# AUDIO_IN_OUT.net
KiCad netlist of a schematic drawn in Altium Designer
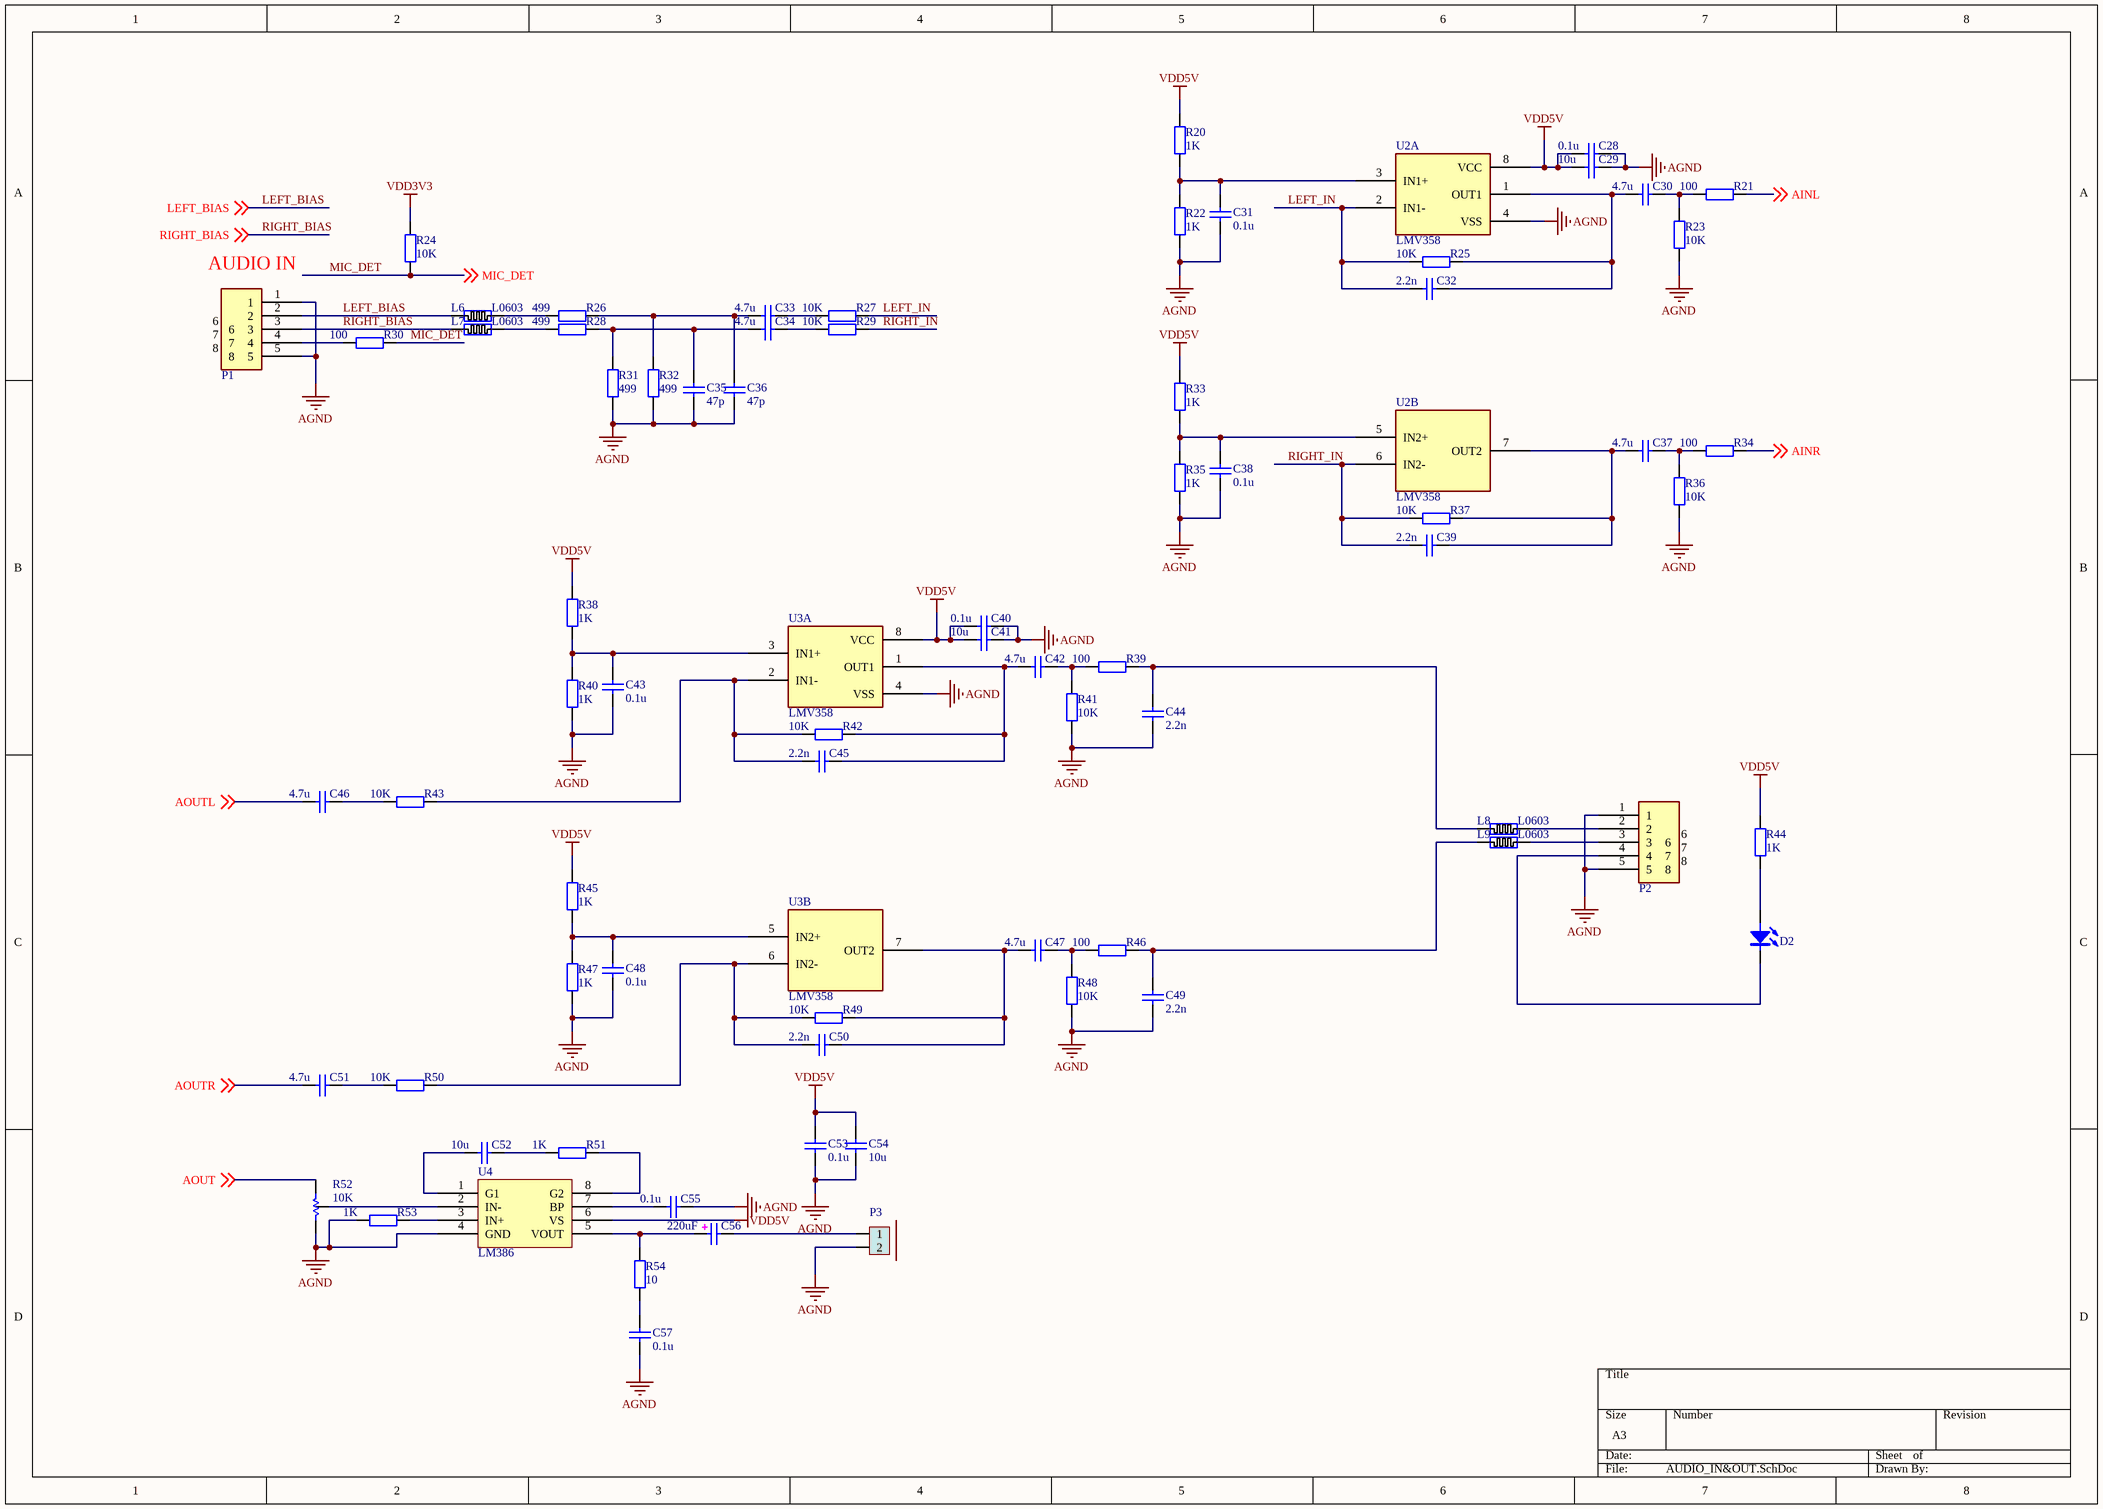
[diagram p0: AUDIO_IN&OUT.SchDoc]

(export (version "E")
  (design (tool "Eeschema 10.0.6"))
  (components
    (comp (ref "C28")
      (value "0.1u")
      (footprint "C0603")
      (description "0603 Capacitor without Polarity")
      (libsource (lib "lpc2368") (part "CAP0603"))
    )
    (comp (ref "C29")
      (value "10u")
      (footprint "C0603")
      (description "0603 Capacitor without Polarity")
      (libsource (lib "lpc2368") (part "CAP0603"))
    )
    (comp (ref "C30")
      (value "4.7u")
      (footprint "C0603")
      (description "0603 Capacitor without Polarity")
      (libsource (lib "lpc2368") (part "CAP0603"))
    )
    (comp (ref "C31")
      (value "0.1u")
      (footprint "C0603")
      (description "0603 Capacitor without Polarity")
      (libsource (lib "lpc2368") (part "CAP0603"))
    )
    (comp (ref "C32")
      (value "2.2n")
      (footprint "C0603")
      (description "0603 Capacitor without Polarity")
      (libsource (lib "lpc2368") (part "CAP0603"))
    )
    (comp (ref "C33")
      (value "4.7u")
      (footprint "C0603")
      (description "0603 Capacitor without Polarity")
      (libsource (lib "lpc2368") (part "CAP0603"))
    )
    (comp (ref "C34")
      (value "4.7u")
      (footprint "C0603")
      (description "0603 Capacitor without Polarity")
      (libsource (lib "lpc2368") (part "CAP0603"))
    )
    (comp (ref "C35")
      (value "47p")
      (footprint "C0603")
      (description "0603 Capacitor without Polarity")
      (libsource (lib "lpc2368") (part "CAP0603"))
    )
    (comp (ref "C36")
      (value "47p")
      (footprint "C0603")
      (description "0603 Capacitor without Polarity")
      (libsource (lib "lpc2368") (part "CAP0603"))
    )
    (comp (ref "C37")
      (value "4.7u")
      (footprint "C0603")
      (description "0603 Capacitor without Polarity")
      (libsource (lib "lpc2368") (part "CAP0603"))
    )
    (comp (ref "C38")
      (value "0.1u")
      (footprint "C0603")
      (description "0603 Capacitor without Polarity")
      (libsource (lib "lpc2368") (part "CAP0603"))
    )
    (comp (ref "C39")
      (value "2.2n")
      (footprint "C0603")
      (description "0603 Capacitor without Polarity")
      (libsource (lib "lpc2368") (part "CAP0603"))
    )
    (comp (ref "C40")
      (value "0.1u")
      (footprint "C0603")
      (description "0603 Capacitor without Polarity")
      (libsource (lib "lpc2368") (part "CAP0603"))
    )
    (comp (ref "C41")
      (value "10u")
      (footprint "C0603")
      (description "0603 Capacitor without Polarity")
      (libsource (lib "lpc2368") (part "CAP0603"))
    )
    (comp (ref "C42")
      (value "4.7u")
      (footprint "C0603")
      (description "0603 Capacitor without Polarity")
      (libsource (lib "lpc2368") (part "CAP0603"))
    )
    (comp (ref "C43")
      (value "0.1u")
      (footprint "C0603")
      (description "0603 Capacitor without Polarity")
      (libsource (lib "lpc2368") (part "CAP0603"))
    )
    (comp (ref "C44")
      (value "2.2n")
      (footprint "C0603")
      (description "0603 Capacitor without Polarity")
      (libsource (lib "lpc2368") (part "CAP0603"))
    )
    (comp (ref "C45")
      (value "2.2n")
      (footprint "C0603")
      (description "0603 Capacitor without Polarity")
      (libsource (lib "lpc2368") (part "CAP0603"))
    )
    (comp (ref "C46")
      (value "4.7u")
      (footprint "C0603")
      (description "0603 Capacitor without Polarity")
      (libsource (lib "lpc2368") (part "CAP0603"))
    )
    (comp (ref "C47")
      (value "4.7u")
      (footprint "C0603")
      (description "0603 Capacitor without Polarity")
      (libsource (lib "lpc2368") (part "CAP0603"))
    )
    (comp (ref "C48")
      (value "0.1u")
      (footprint "C0603")
      (description "0603 Capacitor without Polarity")
      (libsource (lib "lpc2368") (part "CAP0603"))
    )
    (comp (ref "C49")
      (value "2.2n")
      (footprint "C0603")
      (description "0603 Capacitor without Polarity")
      (libsource (lib "lpc2368") (part "CAP0603"))
    )
    (comp (ref "C50")
      (value "2.2n")
      (footprint "C0603")
      (description "0603 Capacitor without Polarity")
      (libsource (lib "lpc2368") (part "CAP0603"))
    )
    (comp (ref "C51")
      (value "4.7u")
      (footprint "C0603")
      (description "0603 Capacitor without Polarity")
      (libsource (lib "lpc2368") (part "CAP0603"))
    )
    (comp (ref "C52")
      (value "10u")
      (footprint "C0603")
      (description "0603 Capacitor without Polarity")
      (libsource (lib "lpc2368") (part "CAP0603"))
    )
    (comp (ref "C53")
      (value "0.1u")
      (footprint "C0603")
      (description "0603 Capacitor without Polarity")
      (libsource (lib "lpc2368") (part "CAP0603"))
    )
    (comp (ref "C54")
      (value "10u")
      (footprint "C0603")
      (description "0603 Capacitor without Polarity")
      (libsource (lib "lpc2368") (part "CAP0603"))
    )
    (comp (ref "C55")
      (value "0.1u")
      (footprint "C0603")
      (description "0603 Capacitor without Polarity")
      (libsource (lib "lpc2368") (part "CAP0603"))
    )
    (comp (ref "C56")
      (value "220uF")
      (footprint "tc")
      (description "钽电容1210封装")
      (libsource (lib "lpc2368") (part "DCAP"))
    )
    (comp (ref "C57")
      (value "0.1u")
      (footprint "C0603")
      (description "0603 Capacitor without Polarity")
      (libsource (lib "lpc2368") (part "CAP0603"))
    )
    (comp (ref "D2")
      (value "LED_SMT")
      (footprint "LED0805")
      (description "贴片发光二极管")
      (libsource (lib "lpc2368") (part "LED_SMT"))
    )
    (comp (ref "L6")
      (value "L0603")
      (footprint "L0603")
      (description "0603 Inductor")
      (libsource (lib "lpc2368") (part "L0603"))
    )
    (comp (ref "L7")
      (value "L0603")
      (footprint "L0603")
      (description "0603 Inductor")
      (libsource (lib "lpc2368") (part "L0603"))
    )
    (comp (ref "L8")
      (value "L0603")
      (footprint "L0603")
      (description "0603 Inductor")
      (libsource (lib "lpc2368") (part "L0603"))
    )
    (comp (ref "L9")
      (value "L0603")
      (footprint "L0603")
      (description "0603 Inductor")
      (libsource (lib "lpc2368") (part "L0603"))
    )
    (comp (ref "P1")
      (value "PHONE JACK")
      (footprint "AUDIO-8P")
      (description "3.5mm AUDIO INPUT CONNECTOR with MIC")
      (libsource (lib "") (part "PHONE JACK_1"))
    )
    (comp (ref "P2")
      (value "PHONE JACK")
      (footprint "AUDIO-8P")
      (description "3.5mm AUDIO INPUT CONNECTOR with MIC")
      (libsource (lib "lpc2368") (part "PHONE JACK"))
    )
    (comp (ref "P3")
      (value "PIN")
      (footprint "SIP2")
      (description "Connectors with two pins")
      (libsource (lib "lpc2368") (part "SIP2"))
    )
    (comp (ref "R20")
      (value "1K")
      (footprint "R0603")
      (description "0603 Resistor")
      (libsource (lib "") (part "RES0603_1"))
    )
    (comp (ref "R21")
      (value "100")
      (footprint "R0603")
      (description "0603 Resistor")
      (libsource (lib "lpc2368") (part "RES0603"))
    )
    (comp (ref "R22")
      (value "1K")
      (footprint "R0603")
      (description "0603 Resistor")
      (libsource (lib "") (part "RES0603_1"))
    )
    (comp (ref "R23")
      (value "10K")
      (footprint "R0603")
      (description "0603 Resistor")
      (libsource (lib "") (part "RES0603_1"))
    )
    (comp (ref "R24")
      (value "10K")
      (footprint "R0603")
      (description "0603 Resistor")
      (libsource (lib "") (part "RES0603_1"))
    )
    (comp (ref "R25")
      (value "10K")
      (footprint "R0603")
      (description "0603 Resistor")
      (libsource (lib "lpc2368") (part "RES0603"))
    )
    (comp (ref "R26")
      (value "499")
      (footprint "R0603")
      (description "0603 Resistor")
      (libsource (lib "lpc2368") (part "RES0603"))
    )
    (comp (ref "R27")
      (value "10K")
      (footprint "R0603")
      (description "0603 Resistor")
      (libsource (lib "lpc2368") (part "RES0603"))
    )
    (comp (ref "R28")
      (value "499")
      (footprint "R0603")
      (description "0603 Resistor")
      (libsource (lib "lpc2368") (part "RES0603"))
    )
    (comp (ref "R29")
      (value "10K")
      (footprint "R0603")
      (description "0603 Resistor")
      (libsource (lib "lpc2368") (part "RES0603"))
    )
    (comp (ref "R30")
      (value "100")
      (footprint "R0603")
      (description "0603 Resistor")
      (libsource (lib "lpc2368") (part "RES0603"))
    )
    (comp (ref "R31")
      (value "499")
      (footprint "R0603")
      (description "0603 Resistor")
      (libsource (lib "") (part "RES0603_1"))
    )
    (comp (ref "R32")
      (value "499")
      (footprint "R0603")
      (description "0603 Resistor")
      (libsource (lib "") (part "RES0603_1"))
    )
    (comp (ref "R33")
      (value "1K")
      (footprint "R0603")
      (description "0603 Resistor")
      (libsource (lib "") (part "RES0603_1"))
    )
    (comp (ref "R34")
      (value "100")
      (footprint "R0603")
      (description "0603 Resistor")
      (libsource (lib "lpc2368") (part "RES0603"))
    )
    (comp (ref "R35")
      (value "1K")
      (footprint "R0603")
      (description "0603 Resistor")
      (libsource (lib "") (part "RES0603_1"))
    )
    (comp (ref "R36")
      (value "10K")
      (footprint "R0603")
      (description "0603 Resistor")
      (libsource (lib "") (part "RES0603_1"))
    )
    (comp (ref "R37")
      (value "10K")
      (footprint "R0603")
      (description "0603 Resistor")
      (libsource (lib "lpc2368") (part "RES0603"))
    )
    (comp (ref "R38")
      (value "1K")
      (footprint "R0603")
      (description "0603 Resistor")
      (libsource (lib "") (part "RES0603_1"))
    )
    (comp (ref "R39")
      (value "100")
      (footprint "R0603")
      (description "0603 Resistor")
      (libsource (lib "lpc2368") (part "RES0603"))
    )
    (comp (ref "R40")
      (value "1K")
      (footprint "R0603")
      (description "0603 Resistor")
      (libsource (lib "") (part "RES0603_1"))
    )
    (comp (ref "R41")
      (value "10K")
      (footprint "R0603")
      (description "0603 Resistor")
      (libsource (lib "") (part "RES0603_1"))
    )
    (comp (ref "R42")
      (value "10K")
      (footprint "R0603")
      (description "0603 Resistor")
      (libsource (lib "lpc2368") (part "RES0603"))
    )
    (comp (ref "R43")
      (value "10K")
      (footprint "R0603")
      (description "0603 Resistor")
      (libsource (lib "lpc2368") (part "RES0603"))
    )
    (comp (ref "R44")
      (value "1K")
      (footprint "R0603")
      (description "0603 Resistor")
      (libsource (lib "") (part "RES0603_1"))
    )
    (comp (ref "R45")
      (value "1K")
      (footprint "R0603")
      (description "0603 Resistor")
      (libsource (lib "") (part "RES0603_1"))
    )
    (comp (ref "R46")
      (value "100")
      (footprint "R0603")
      (description "0603 Resistor")
      (libsource (lib "lpc2368") (part "RES0603"))
    )
    (comp (ref "R47")
      (value "1K")
      (footprint "R0603")
      (description "0603 Resistor")
      (libsource (lib "") (part "RES0603_1"))
    )
    (comp (ref "R48")
      (value "10K")
      (footprint "R0603")
      (description "0603 Resistor")
      (libsource (lib "") (part "RES0603_1"))
    )
    (comp (ref "R49")
      (value "10K")
      (footprint "R0603")
      (description "0603 Resistor")
      (libsource (lib "lpc2368") (part "RES0603"))
    )
    (comp (ref "R50")
      (value "10K")
      (footprint "R0603")
      (description "0603 Resistor")
      (libsource (lib "lpc2368") (part "RES0603"))
    )
    (comp (ref "R51")
      (value "1K")
      (footprint "R0603")
      (description "0603 Resistor")
      (libsource (lib "lpc2368") (part "RES0603"))
    )
    (comp (ref "R52")
      (value "10K")
      (footprint "RSET-SMT")
      (description "直插式可调电阻")
      (libsource (lib "lpc2368") (part "Res1"))
    )
    (comp (ref "R53")
      (value "1K")
      (footprint "R0603")
      (description "0603 Resistor")
      (libsource (lib "lpc2368") (part "RES0603"))
    )
    (comp (ref "R54")
      (value "10")
      (footprint "R0603")
      (description "0603 Resistor")
      (libsource (lib "") (part "RES0603_1"))
    )
    (comp (ref "U2")
      (value "LMV358")
      (footprint "SO8/D/R-PDSO-G8")
      (description "AMP")
      (libsource (lib "lpc2368") (part "LMV358"))
    )
    (comp (ref "U3")
      (value "LMV358")
      (footprint "SO8/D/R-PDSO-G8")
      (description "AMP")
      (libsource (lib "lpc2368") (part "LMV358"))
    )
    (comp (ref "U4") (value "LM386") (footprint "SO8/D/R-PDSO-G8") (libsource (lib "lpc2368") (part "LM386")))
  )
  (nets
    (net (code "1") (name "/LEFT_IN") (class "Default")
      (node (ref "C32") (pin "1") (pinfunction "1_1") (pintype "passive"))
      (node (ref "R25") (pin "1") (pinfunction "1_1") (pintype "passive"))
      (node (ref "R27") (pin "2") (pinfunction "2_2") (pintype "passive"))
      (node (ref "U2") (pin "2") (pinfunction "IN1-_2") (pintype "passive"))
    )
    (net (code "2") (name "/RIGHT_IN") (class "Default")
      (node (ref "C39") (pin "1") (pinfunction "1_1") (pintype "passive"))
      (node (ref "R29") (pin "2") (pinfunction "2_2") (pintype "passive"))
      (node (ref "R37") (pin "1") (pinfunction "1_1") (pintype "passive"))
      (node (ref "U2") (pin "6") (pinfunction "IN2-_6") (pintype "passive"))
    )
    (net (code "3") (name "AGND") (class "Default")
      (node (ref "C28") (pin "2") (pinfunction "2_2") (pintype "passive"))
      (node (ref "C29") (pin "2") (pinfunction "2_2") (pintype "passive"))
      (node (ref "C31") (pin "2") (pinfunction "2_2") (pintype "passive"))
      (node (ref "C35") (pin "2") (pinfunction "2_2") (pintype "passive"))
      (node (ref "C36") (pin "2") (pinfunction "2_2") (pintype "passive"))
      (node (ref "C38") (pin "2") (pinfunction "2_2") (pintype "passive"))
      (node (ref "C40") (pin "2") (pinfunction "2_2") (pintype "passive"))
      (node (ref "C41") (pin "2") (pinfunction "2_2") (pintype "passive"))
      (node (ref "C43") (pin "2") (pinfunction "2_2") (pintype "passive"))
      (node (ref "C44") (pin "1") (pinfunction "1_1") (pintype "passive"))
      (node (ref "C48") (pin "2") (pinfunction "2_2") (pintype "passive"))
      (node (ref "C49") (pin "1") (pinfunction "1_1") (pintype "passive"))
      (node (ref "C53") (pin "1") (pinfunction "1_1") (pintype "passive"))
      (node (ref "C54") (pin "1") (pinfunction "1_1") (pintype "passive"))
      (node (ref "C55") (pin "2") (pinfunction "2_2") (pintype "passive"))
      (node (ref "C57") (pin "2") (pinfunction "2_2") (pintype "passive"))
      (node (ref "P1") (pin "1") (pinfunction "1_1") (pintype "passive"))
      (node (ref "P1") (pin "5") (pinfunction "5_5") (pintype "passive"))
      (node (ref "P2") (pin "1") (pinfunction "1_1") (pintype "passive"))
      (node (ref "P2") (pin "5") (pinfunction "5_5") (pintype "passive"))
      (node (ref "P3") (pin "2") (pinfunction "2_2") (pintype "passive"))
      (node (ref "R22") (pin "1") (pinfunction "1_1") (pintype "passive"))
      (node (ref "R23") (pin "1") (pinfunction "1_1") (pintype "passive"))
      (node (ref "R31") (pin "1") (pinfunction "1_1") (pintype "passive"))
      (node (ref "R32") (pin "1") (pinfunction "1_1") (pintype "passive"))
      (node (ref "R35") (pin "1") (pinfunction "1_1") (pintype "passive"))
      (node (ref "R36") (pin "1") (pinfunction "1_1") (pintype "passive"))
      (node (ref "R40") (pin "1") (pinfunction "1_1") (pintype "passive"))
      (node (ref "R41") (pin "1") (pinfunction "1_1") (pintype "passive"))
      (node (ref "R47") (pin "1") (pinfunction "1_1") (pintype "passive"))
      (node (ref "R48") (pin "1") (pinfunction "1_1") (pintype "passive"))
      (node (ref "R52") (pin "1") (pinfunction "1_1") (pintype "passive"))
      (node (ref "R53") (pin "1") (pinfunction "1_1") (pintype "passive"))
      (node (ref "U2") (pin "4") (pinfunction "VSS_4") (pintype "passive"))
      (node (ref "U3") (pin "4") (pinfunction "VSS_4") (pintype "passive"))
      (node (ref "U4") (pin "4") (pinfunction "GND_4") (pintype "passive"))
    )
    (net (code "4") (name "AINL") (class "Default")
      (node (ref "R21") (pin "2") (pinfunction "2_2") (pintype "passive"))
    )
    (net (code "5") (name "AINR") (class "Default")
      (node (ref "R34") (pin "2") (pinfunction "2_2") (pintype "passive"))
    )
    (net (code "6") (name "AOUT") (class "Default")
      (node (ref "R52") (pin "3") (pinfunction "3_3") (pintype "passive"))
    )
    (net (code "7") (name "AOUTL") (class "Default")
      (node (ref "C46") (pin "1") (pinfunction "1_1") (pintype "passive"))
    )
    (net (code "8") (name "AOUTR") (class "Default")
      (node (ref "C51") (pin "1") (pinfunction "1_1") (pintype "passive"))
    )
    (net (code "9") (name "LEFT_BIAS") (class "Default")
      (node (ref "L6") (pin "1") (pinfunction "1_1") (pintype "passive"))
      (node (ref "P1") (pin "2") (pinfunction "2_2") (pintype "passive"))
    )
    (net (code "10") (name "MIC_DET") (class "Default")
      (node (ref "R24") (pin "1") (pinfunction "1_1") (pintype "passive"))
      (node (ref "R30") (pin "2") (pinfunction "2_2") (pintype "passive"))
    )
    (net (code "11") (name "Net-(C30-Pad2)") (class "Default")
      (node (ref "C30") (pin "2") (pinfunction "2_2") (pintype "passive"))
      (node (ref "R21") (pin "1") (pinfunction "1_1") (pintype "passive"))
      (node (ref "R23") (pin "2") (pinfunction "2_2") (pintype "passive"))
    )
    (net (code "12") (name "Net-(C33-Pad1)") (class "Default")
      (node (ref "C33") (pin "1") (pinfunction "1_1") (pintype "passive"))
      (node (ref "C36") (pin "1") (pinfunction "1_1") (pintype "passive"))
      (node (ref "R26") (pin "2") (pinfunction "2_2") (pintype "passive"))
      (node (ref "R32") (pin "2") (pinfunction "2_2") (pintype "passive"))
    )
    (net (code "13") (name "Net-(C33-Pad2)") (class "Default")
      (node (ref "C33") (pin "2") (pinfunction "2_2") (pintype "passive"))
      (node (ref "R27") (pin "1") (pinfunction "1_1") (pintype "passive"))
    )
    (net (code "14") (name "Net-(C34-Pad1)") (class "Default")
      (node (ref "C34") (pin "1") (pinfunction "1_1") (pintype "passive"))
      (node (ref "C35") (pin "1") (pinfunction "1_1") (pintype "passive"))
      (node (ref "R28") (pin "2") (pinfunction "2_2") (pintype "passive"))
      (node (ref "R31") (pin "2") (pinfunction "2_2") (pintype "passive"))
    )
    (net (code "15") (name "Net-(C34-Pad2)") (class "Default")
      (node (ref "C34") (pin "2") (pinfunction "2_2") (pintype "passive"))
      (node (ref "R29") (pin "1") (pinfunction "1_1") (pintype "passive"))
    )
    (net (code "16") (name "Net-(C37-Pad2)") (class "Default")
      (node (ref "C37") (pin "2") (pinfunction "2_2") (pintype "passive"))
      (node (ref "R34") (pin "1") (pinfunction "1_1") (pintype "passive"))
      (node (ref "R36") (pin "2") (pinfunction "2_2") (pintype "passive"))
    )
    (net (code "17") (name "Net-(C42-Pad2)") (class "Default")
      (node (ref "C42") (pin "2") (pinfunction "2_2") (pintype "passive"))
      (node (ref "R39") (pin "1") (pinfunction "1_1") (pintype "passive"))
      (node (ref "R41") (pin "2") (pinfunction "2_2") (pintype "passive"))
    )
    (net (code "18") (name "Net-(C44-Pad2)") (class "Default")
      (node (ref "C44") (pin "2") (pinfunction "2_2") (pintype "passive"))
      (node (ref "L8") (pin "1") (pinfunction "1_1") (pintype "passive"))
      (node (ref "R39") (pin "2") (pinfunction "2_2") (pintype "passive"))
    )
    (net (code "19") (name "Net-(C46-Pad2)") (class "Default")
      (node (ref "C46") (pin "2") (pinfunction "2_2") (pintype "passive"))
      (node (ref "R43") (pin "1") (pinfunction "1_1") (pintype "passive"))
    )
    (net (code "20") (name "Net-(C47-Pad2)") (class "Default")
      (node (ref "C47") (pin "2") (pinfunction "2_2") (pintype "passive"))
      (node (ref "R46") (pin "1") (pinfunction "1_1") (pintype "passive"))
      (node (ref "R48") (pin "2") (pinfunction "2_2") (pintype "passive"))
    )
    (net (code "21") (name "Net-(C49-Pad2)") (class "Default")
      (node (ref "C49") (pin "2") (pinfunction "2_2") (pintype "passive"))
      (node (ref "L9") (pin "1") (pinfunction "1_1") (pintype "passive"))
      (node (ref "R46") (pin "2") (pinfunction "2_2") (pintype "passive"))
    )
    (net (code "22") (name "Net-(C51-Pad2)") (class "Default")
      (node (ref "C51") (pin "2") (pinfunction "2_2") (pintype "passive"))
      (node (ref "R50") (pin "1") (pinfunction "1_1") (pintype "passive"))
    )
    (net (code "23") (name "Net-(C52-Pad2)") (class "Default")
      (node (ref "C52") (pin "2") (pinfunction "2_2") (pintype "passive"))
      (node (ref "R51") (pin "1") (pinfunction "1_1") (pintype "passive"))
    )
    (net (code "24") (name "Net-(C56-Pad2)") (class "Default")
      (node (ref "C56") (pin "2") (pinfunction "2_2") (pintype "passive"))
      (node (ref "P3") (pin "1") (pinfunction "1_1") (pintype "passive"))
    )
    (net (code "25") (name "Net-(C57-Pad1)") (class "Default")
      (node (ref "C57") (pin "1") (pinfunction "1_1") (pintype "passive"))
      (node (ref "R54") (pin "1") (pinfunction "1_1") (pintype "passive"))
    )
    (net (code "26") (name "Net-(D2-PadA)") (class "Default")
      (node (ref "D2") (pin "A") (pinfunction "A_A") (pintype "passive"))
      (node (ref "R44") (pin "1") (pinfunction "1_1") (pintype "passive"))
    )
    (net (code "27") (name "Net-(D2-PadK)") (class "Default")
      (node (ref "D2") (pin "K") (pinfunction "K_K") (pintype "passive"))
      (node (ref "P2") (pin "4") (pinfunction "4_4") (pintype "passive"))
    )
    (net (code "28") (name "Net-(L6-Pad2)") (class "Default")
      (node (ref "L6") (pin "2") (pinfunction "2_2") (pintype "passive"))
      (node (ref "R26") (pin "1") (pinfunction "1_1") (pintype "passive"))
    )
    (net (code "29") (name "Net-(L7-Pad2)") (class "Default")
      (node (ref "L7") (pin "2") (pinfunction "2_2") (pintype "passive"))
      (node (ref "R28") (pin "1") (pinfunction "1_1") (pintype "passive"))
    )
    (net (code "30") (name "Net-(L8-Pad2)") (class "Default")
      (node (ref "L8") (pin "2") (pinfunction "2_2") (pintype "passive"))
      (node (ref "P2") (pin "2") (pinfunction "2_2") (pintype "passive"))
    )
    (net (code "31") (name "Net-(L9-Pad2)") (class "Default")
      (node (ref "L9") (pin "2") (pinfunction "2_2") (pintype "passive"))
      (node (ref "P2") (pin "3") (pinfunction "3_3") (pintype "passive"))
    )
    (net (code "32") (name "Net-(P1-Pad4)") (class "Default")
      (node (ref "P1") (pin "4") (pinfunction "4_4") (pintype "passive"))
      (node (ref "R30") (pin "1") (pinfunction "1_1") (pintype "passive"))
    )
    (net (code "33") (name "Net-(U2A-IN1+)") (class "Default")
      (node (ref "C31") (pin "1") (pinfunction "1_1") (pintype "passive"))
      (node (ref "R20") (pin "1") (pinfunction "1_1") (pintype "passive"))
      (node (ref "R22") (pin "2") (pinfunction "2_2") (pintype "passive"))
      (node (ref "U2") (pin "3") (pinfunction "IN1+_3") (pintype "passive"))
    )
    (net (code "34") (name "Net-(U2A-OUT1)") (class "Default")
      (node (ref "C30") (pin "1") (pinfunction "1_1") (pintype "passive"))
      (node (ref "C32") (pin "2") (pinfunction "2_2") (pintype "passive"))
      (node (ref "R25") (pin "2") (pinfunction "2_2") (pintype "passive"))
      (node (ref "U2") (pin "1") (pinfunction "OUT1_1") (pintype "passive"))
    )
    (net (code "35") (name "Net-(U2B-IN2+)") (class "Default")
      (node (ref "C38") (pin "1") (pinfunction "1_1") (pintype "passive"))
      (node (ref "R33") (pin "1") (pinfunction "1_1") (pintype "passive"))
      (node (ref "R35") (pin "2") (pinfunction "2_2") (pintype "passive"))
      (node (ref "U2") (pin "5") (pinfunction "IN2+_5") (pintype "passive"))
    )
    (net (code "36") (name "Net-(U2B-OUT2)") (class "Default")
      (node (ref "C37") (pin "1") (pinfunction "1_1") (pintype "passive"))
      (node (ref "C39") (pin "2") (pinfunction "2_2") (pintype "passive"))
      (node (ref "R37") (pin "2") (pinfunction "2_2") (pintype "passive"))
      (node (ref "U2") (pin "7") (pinfunction "OUT2_7") (pintype "passive"))
    )
    (net (code "37") (name "Net-(U3A-IN1+)") (class "Default")
      (node (ref "C43") (pin "1") (pinfunction "1_1") (pintype "passive"))
      (node (ref "R38") (pin "1") (pinfunction "1_1") (pintype "passive"))
      (node (ref "R40") (pin "2") (pinfunction "2_2") (pintype "passive"))
      (node (ref "U3") (pin "3") (pinfunction "IN1+_3") (pintype "passive"))
    )
    (net (code "38") (name "Net-(U3A-IN1-)") (class "Default")
      (node (ref "C45") (pin "1") (pinfunction "1_1") (pintype "passive"))
      (node (ref "R42") (pin "1") (pinfunction "1_1") (pintype "passive"))
      (node (ref "R43") (pin "2") (pinfunction "2_2") (pintype "passive"))
      (node (ref "U3") (pin "2") (pinfunction "IN1-_2") (pintype "passive"))
    )
    (net (code "39") (name "Net-(U3A-OUT1)") (class "Default")
      (node (ref "C42") (pin "1") (pinfunction "1_1") (pintype "passive"))
      (node (ref "C45") (pin "2") (pinfunction "2_2") (pintype "passive"))
      (node (ref "R42") (pin "2") (pinfunction "2_2") (pintype "passive"))
      (node (ref "U3") (pin "1") (pinfunction "OUT1_1") (pintype "passive"))
    )
    (net (code "40") (name "Net-(U3B-IN2+)") (class "Default")
      (node (ref "C48") (pin "1") (pinfunction "1_1") (pintype "passive"))
      (node (ref "R45") (pin "1") (pinfunction "1_1") (pintype "passive"))
      (node (ref "R47") (pin "2") (pinfunction "2_2") (pintype "passive"))
      (node (ref "U3") (pin "5") (pinfunction "IN2+_5") (pintype "passive"))
    )
    (net (code "41") (name "Net-(U3B-IN2-)") (class "Default")
      (node (ref "C50") (pin "1") (pinfunction "1_1") (pintype "passive"))
      (node (ref "R49") (pin "1") (pinfunction "1_1") (pintype "passive"))
      (node (ref "R50") (pin "2") (pinfunction "2_2") (pintype "passive"))
      (node (ref "U3") (pin "6") (pinfunction "IN2-_6") (pintype "passive"))
    )
    (net (code "42") (name "Net-(U3B-OUT2)") (class "Default")
      (node (ref "C47") (pin "1") (pinfunction "1_1") (pintype "passive"))
      (node (ref "C50") (pin "2") (pinfunction "2_2") (pintype "passive"))
      (node (ref "R49") (pin "2") (pinfunction "2_2") (pintype "passive"))
      (node (ref "U3") (pin "7") (pinfunction "OUT2_7") (pintype "passive"))
    )
    (net (code "43") (name "Net-(U4-BP)") (class "Default")
      (node (ref "C55") (pin "1") (pinfunction "1_1") (pintype "passive"))
      (node (ref "U4") (pin "7") (pinfunction "BP_7") (pintype "passive"))
    )
    (net (code "44") (name "Net-(U4-G1)") (class "Default")
      (node (ref "C52") (pin "1") (pinfunction "1_1") (pintype "passive"))
      (node (ref "U4") (pin "1") (pinfunction "G1_1") (pintype "passive"))
    )
    (net (code "45") (name "Net-(U4-G2)") (class "Default")
      (node (ref "R51") (pin "2") (pinfunction "2_2") (pintype "passive"))
      (node (ref "U4") (pin "8") (pinfunction "G2_8") (pintype "passive"))
    )
    (net (code "46") (name "Net-(U4-IN+)") (class "Default")
      (node (ref "R53") (pin "2") (pinfunction "2_2") (pintype "passive"))
      (node (ref "U4") (pin "3") (pinfunction "IN+_3") (pintype "passive"))
    )
    (net (code "47") (name "Net-(U4-IN-)") (class "Default")
      (node (ref "R52") (pin "2") (pinfunction "2_2") (pintype "passive"))
      (node (ref "U4") (pin "2") (pinfunction "IN-_2") (pintype "passive"))
    )
    (net (code "48") (name "Net-(U4-VOUT)") (class "Default")
      (node (ref "C56") (pin "1") (pinfunction "1_1") (pintype "passive"))
      (node (ref "R54") (pin "2") (pinfunction "2_2") (pintype "passive"))
      (node (ref "U4") (pin "5") (pinfunction "VOUT_5") (pintype "passive"))
    )
    (net (code "49") (name "RIGHT_BIAS") (class "Default")
      (node (ref "L7") (pin "1") (pinfunction "1_1") (pintype "passive"))
      (node (ref "P1") (pin "3") (pinfunction "3_3") (pintype "passive"))
    )
    (net (code "50") (name "VDD3V3") (class "Default")
      (node (ref "R24") (pin "2") (pinfunction "2_2") (pintype "passive"))
    )
    (net (code "51") (name "VDD5V") (class "Default")
      (node (ref "C28") (pin "1") (pinfunction "1_1") (pintype "passive"))
      (node (ref "C29") (pin "1") (pinfunction "1_1") (pintype "passive"))
      (node (ref "C40") (pin "1") (pinfunction "1_1") (pintype "passive"))
      (node (ref "C41") (pin "1") (pinfunction "1_1") (pintype "passive"))
      (node (ref "C53") (pin "2") (pinfunction "2_2") (pintype "passive"))
      (node (ref "C54") (pin "2") (pinfunction "2_2") (pintype "passive"))
      (node (ref "R20") (pin "2") (pinfunction "2_2") (pintype "passive"))
      (node (ref "R33") (pin "2") (pinfunction "2_2") (pintype "passive"))
      (node (ref "R38") (pin "2") (pinfunction "2_2") (pintype "passive"))
      (node (ref "R44") (pin "2") (pinfunction "2_2") (pintype "passive"))
      (node (ref "R45") (pin "2") (pinfunction "2_2") (pintype "passive"))
      (node (ref "U2") (pin "8") (pinfunction "VCC_8") (pintype "passive"))
      (node (ref "U3") (pin "8") (pinfunction "VCC_8") (pintype "passive"))
      (node (ref "U4") (pin "6") (pinfunction "VS_6") (pintype "passive"))
    )
    (net (code "52") (name "unconnected-(P1-Pad6)") (class "Default")
      (node (ref "P1") (pin "6") (pinfunction "6_6") (pintype "passive"))
    )
    (net (code "53") (name "unconnected-(P1-Pad7)") (class "Default")
      (node (ref "P1") (pin "7") (pinfunction "7_7") (pintype "passive"))
    )
    (net (code "54") (name "unconnected-(P1-Pad8)") (class "Default")
      (node (ref "P1") (pin "8") (pinfunction "8_8") (pintype "passive"))
    )
    (net (code "55") (name "unconnected-(P2-Pad6)") (class "Default")
      (node (ref "P2") (pin "6") (pinfunction "6_6") (pintype "passive"))
    )
    (net (code "56") (name "unconnected-(P2-Pad7)") (class "Default")
      (node (ref "P2") (pin "7") (pinfunction "7_7") (pintype "passive"))
    )
    (net (code "57") (name "unconnected-(P2-Pad8)") (class "Default")
      (node (ref "P2") (pin "8") (pinfunction "8_8") (pintype "passive"))
    )
  )
)
